# working.net
KiCad netlist of a schematic drawn in EAGLE
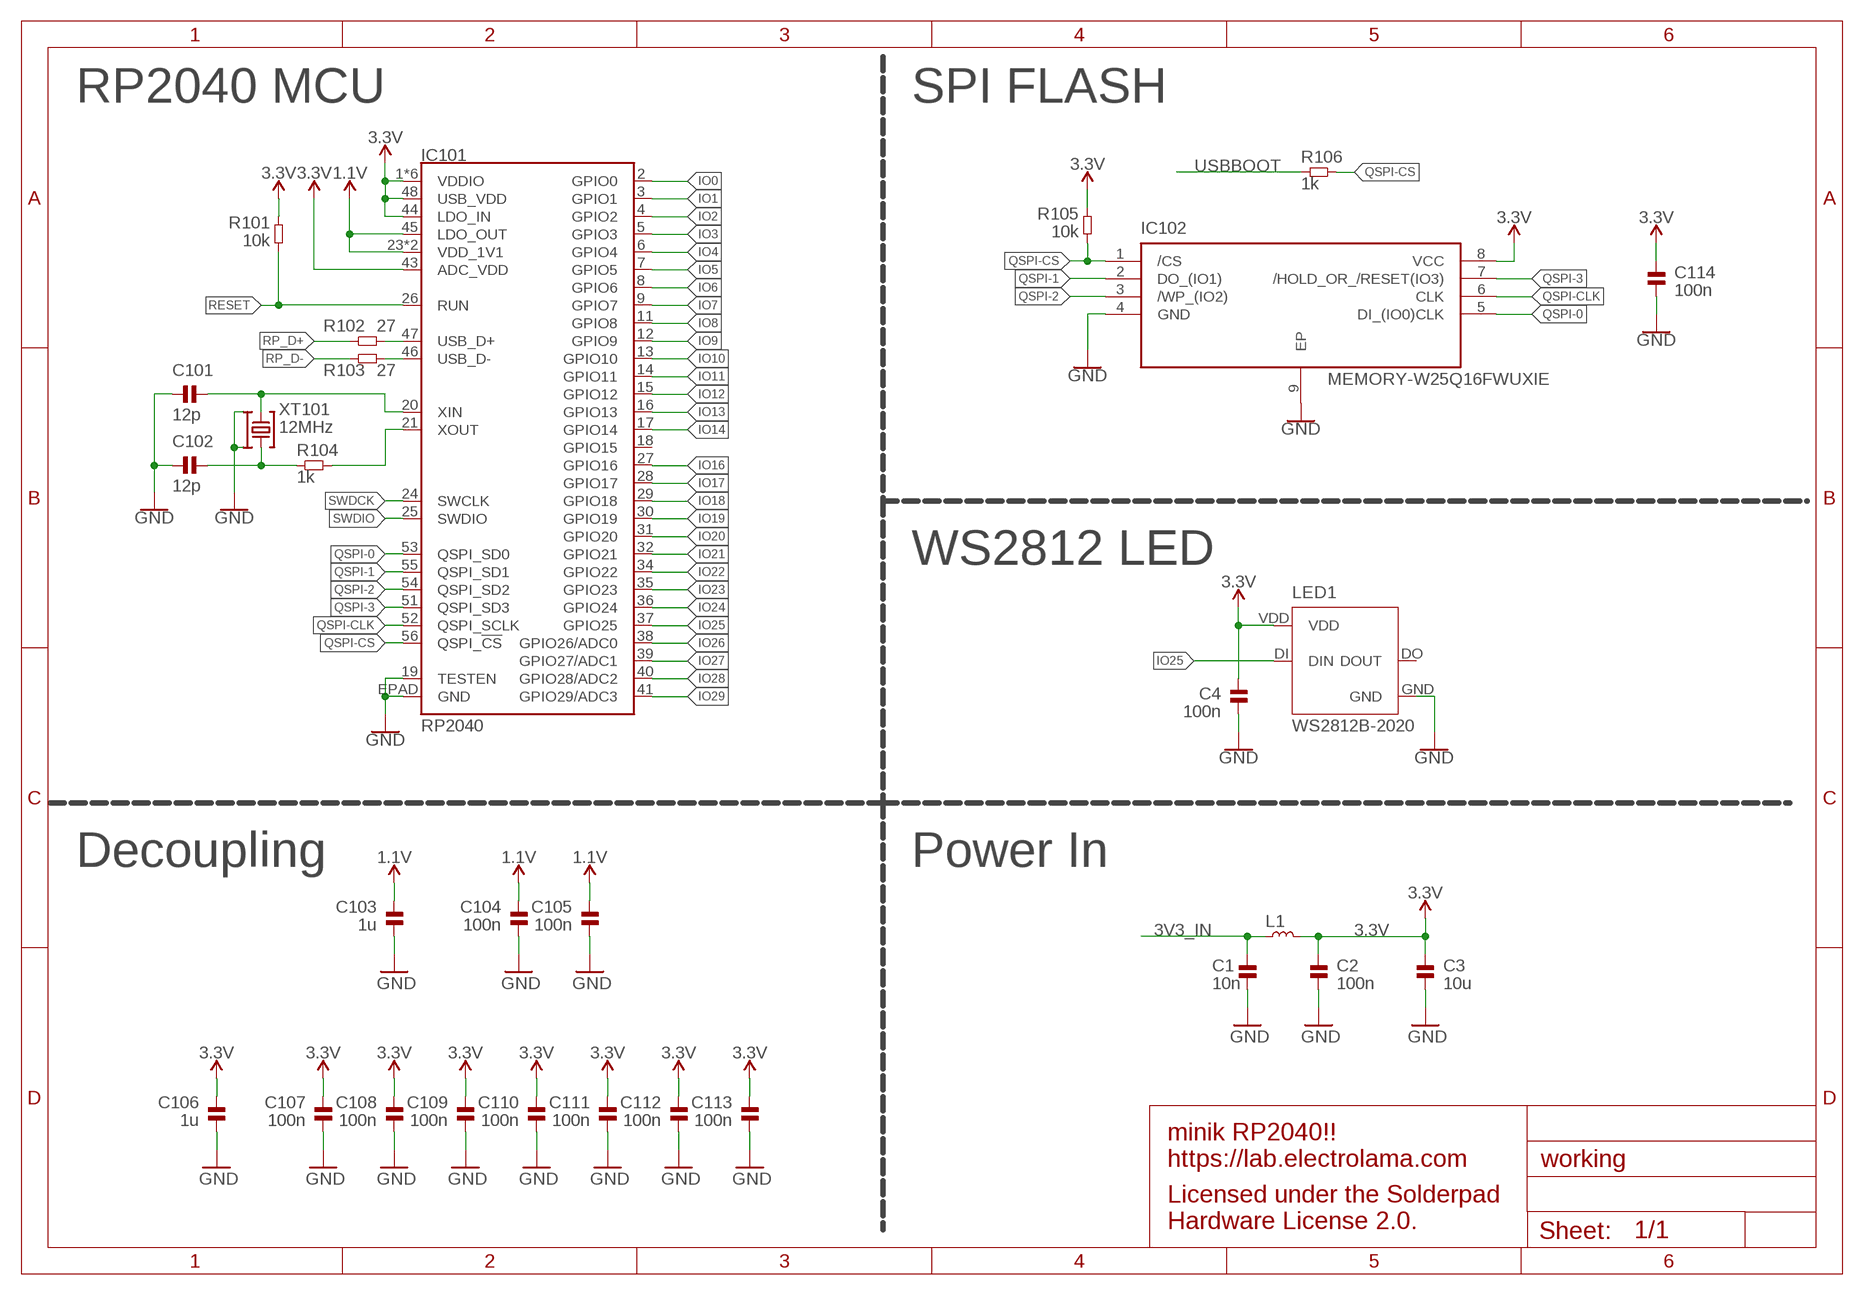
[diagram p0: schematic, sheet 1]

(export (version "E")
  (design (tool "Eeschema 10.0.6"))
  (components
    (comp (ref "C1")
      (value "10n")
      (footprint "eagle-import:_PKG_C_0402")
      (libsource (lib "eagle-import") (part "CAP-0402"))
    )
    (comp (ref "C2")
      (value "100n")
      (footprint "eagle-import:_PKG_C_0402")
      (libsource (lib "eagle-import") (part "CAP-0402"))
    )
    (comp (ref "C3")
      (value "10u")
      (footprint "eagle-import:_PKG_C_0402")
      (libsource (lib "eagle-import") (part "CAP-0402"))
    )
    (comp (ref "C4")
      (value "100n")
      (footprint "eagle-import:_PKG_C_0402")
      (libsource (lib "eagle-import") (part "CAP-0402"))
    )
    (comp (ref "C101")
      (value "12p")
      (footprint "eagle-import:_PKG_C_0402")
      (libsource (lib "eagle-import") (part "CAP-0402"))
    )
    (comp (ref "C102")
      (value "12p")
      (footprint "eagle-import:_PKG_C_0402")
      (libsource (lib "eagle-import") (part "CAP-0402"))
    )
    (comp (ref "C103")
      (value "1u")
      (footprint "eagle-import:_PKG_C_0402")
      (libsource (lib "eagle-import") (part "CAP-0402"))
    )
    (comp (ref "C104")
      (value "100n")
      (footprint "eagle-import:_PKG_C_0402")
      (libsource (lib "eagle-import") (part "CAP-0402"))
    )
    (comp (ref "C105")
      (value "100n")
      (footprint "eagle-import:_PKG_C_0402")
      (libsource (lib "eagle-import") (part "CAP-0402"))
    )
    (comp (ref "C106")
      (value "1u")
      (footprint "eagle-import:_PKG_C_0402")
      (libsource (lib "eagle-import") (part "CAP-0402"))
    )
    (comp (ref "C107")
      (value "100n")
      (footprint "eagle-import:_PKG_C_0402")
      (libsource (lib "eagle-import") (part "CAP-0402"))
    )
    (comp (ref "C108")
      (value "100n")
      (footprint "eagle-import:_PKG_C_0402")
      (libsource (lib "eagle-import") (part "CAP-0402"))
    )
    (comp (ref "C109")
      (value "100n")
      (footprint "eagle-import:_PKG_C_0402")
      (libsource (lib "eagle-import") (part "CAP-0402"))
    )
    (comp (ref "C110")
      (value "100n")
      (footprint "eagle-import:_PKG_C_0402")
      (libsource (lib "eagle-import") (part "CAP-0402"))
    )
    (comp (ref "C111")
      (value "100n")
      (footprint "eagle-import:_PKG_C_0402")
      (libsource (lib "eagle-import") (part "CAP-0402"))
    )
    (comp (ref "C112")
      (value "100n")
      (footprint "eagle-import:_PKG_C_0402")
      (libsource (lib "eagle-import") (part "CAP-0402"))
    )
    (comp (ref "C113")
      (value "100n")
      (footprint "eagle-import:_PKG_C_0402")
      (libsource (lib "eagle-import") (part "CAP-0402"))
    )
    (comp (ref "C114")
      (value "100n")
      (footprint "eagle-import:_PKG_C_0402")
      (libsource (lib "eagle-import") (part "CAP-0402"))
    )
    (comp (ref "IC101")
      (value "RP2040")
      (footprint "eagle-import:QFN-56")
      (libsource (lib "eagle-import") (part "RP2040"))
    )
    (comp (ref "IC102")
      (value "MEMORY-W25Q16FWUXIE")
      (footprint "eagle-import:SON50P300X200X60-9N")
      (fields
        (field (name "ARROW_PART_NUMBER") "W25Q16FWUXIE TR")
        (field (name "MOUSER_PART_NUMBER") "454-W25Q16FWUXIETR")
      )
      (libsource (lib "eagle-import") (part "MEMORY-W25Q16FWUXIE"))
    )
    (comp (ref "L1")
      (value "INDUCTOR-0402")
      (footprint "eagle-import:_PKG_L_0402")
      (libsource (lib "eagle-import") (part "INDUCTOR-0402"))
    )
    (comp (ref "LED1")
      (value "WS2812B-2020")
      (footprint "eagle-import:WS2812B-2020")
      (libsource (lib "eagle-import") (part "WS2812B-2020"))
    )
    (comp (ref "R101")
      (value "10k")
      (footprint "eagle-import:_PKG_R_0402")
      (libsource (lib "eagle-import") (part "RES-0402"))
    )
    (comp (ref "R102")
      (value "27")
      (footprint "eagle-import:_PKG_R_0402")
      (libsource (lib "eagle-import") (part "RES-0402"))
    )
    (comp (ref "R103")
      (value "27")
      (footprint "eagle-import:_PKG_R_0402")
      (libsource (lib "eagle-import") (part "RES-0402"))
    )
    (comp (ref "R104")
      (value "1k")
      (footprint "eagle-import:_PKG_R_0402")
      (libsource (lib "eagle-import") (part "RES-0402"))
    )
    (comp (ref "R105")
      (value "10k")
      (footprint "eagle-import:_PKG_R_0402")
      (libsource (lib "eagle-import") (part "RES-0402"))
    )
    (comp (ref "R106")
      (value "1k")
      (footprint "eagle-import:_PKG_R_0402")
      (libsource (lib "eagle-import") (part "RES-0402"))
    )
    (comp (ref "XT101")
      (value "12MHz")
      (footprint "eagle-import:XTAL-4P-3225")
      (libsource (lib "eagle-import") (part "XTAL-4P-3225"))
    )
  )
  (nets
    (net (code "1") (name "/3V3_IN") (class "Default")
      (node (ref "C1") (pin "2") (pinfunction "2_2") (pintype "passive"))
      (node (ref "L1") (pin "1") (pinfunction "1_1") (pintype "passive"))
    )
    (net (code "2") (name "/USBBOOT") (class "Default")
      (node (ref "R106") (pin "2") (pinfunction "2_2") (pintype "passive"))
    )
    (net (code "3") (name "1.1V") (class "Default")
      (node (ref "C103") (pin "2") (pinfunction "2_2") (pintype "passive"))
      (node (ref "C104") (pin "2") (pinfunction "2_2") (pintype "passive"))
      (node (ref "C105") (pin "2") (pinfunction "2_2") (pintype "passive"))
      (node (ref "IC101") (pin "23") (pinfunction "VDD_1V1_23") (pintype "bidirectional"))
      (node (ref "IC101") (pin "45") (pinfunction "LDO_OUT_45") (pintype "bidirectional"))
      (node (ref "IC101") (pin "50") (pinfunction "VDD_1V1_50") (pintype "bidirectional"))
    )
    (net (code "4") (name "3.3V") (class "Default")
      (node (ref "C106") (pin "2") (pinfunction "2_2") (pintype "passive"))
      (node (ref "C107") (pin "2") (pinfunction "2_2") (pintype "passive"))
      (node (ref "C108") (pin "2") (pinfunction "2_2") (pintype "passive"))
      (node (ref "C109") (pin "2") (pinfunction "2_2") (pintype "passive"))
      (node (ref "C110") (pin "2") (pinfunction "2_2") (pintype "passive"))
      (node (ref "C111") (pin "2") (pinfunction "2_2") (pintype "passive"))
      (node (ref "C112") (pin "2") (pinfunction "2_2") (pintype "passive"))
      (node (ref "C113") (pin "2") (pinfunction "2_2") (pintype "passive"))
      (node (ref "C114") (pin "2") (pinfunction "2_2") (pintype "passive"))
      (node (ref "C2") (pin "2") (pinfunction "2_2") (pintype "passive"))
      (node (ref "C3") (pin "2") (pinfunction "2_2") (pintype "passive"))
      (node (ref "C4") (pin "2") (pinfunction "2_2") (pintype "passive"))
      (node (ref "IC101") (pin "1") (pinfunction "VDDIO_1") (pintype "bidirectional"))
      (node (ref "IC101") (pin "10") (pinfunction "VDDIO_10") (pintype "bidirectional"))
      (node (ref "IC101") (pin "22") (pinfunction "VDDIO_22") (pintype "bidirectional"))
      (node (ref "IC101") (pin "33") (pinfunction "VDDIO_33") (pintype "bidirectional"))
      (node (ref "IC101") (pin "42") (pinfunction "VDDIO_42") (pintype "bidirectional"))
      (node (ref "IC101") (pin "43") (pinfunction "ADC_VDD_43") (pintype "bidirectional"))
      (node (ref "IC101") (pin "44") (pinfunction "LDO_IN_44") (pintype "bidirectional"))
      (node (ref "IC101") (pin "48") (pinfunction "USB_VDD_48") (pintype "bidirectional"))
      (node (ref "IC101") (pin "49") (pinfunction "VDDIO_49") (pintype "bidirectional"))
      (node (ref "IC102") (pin "8") (pinfunction "VCC_8") (pintype "bidirectional"))
      (node (ref "L1") (pin "2") (pinfunction "2_2") (pintype "passive"))
      (node (ref "LED1") (pin "VDD") (pinfunction "VDD_VDD") (pintype "bidirectional"))
      (node (ref "R101") (pin "2") (pinfunction "2_2") (pintype "passive"))
      (node (ref "R105") (pin "2") (pinfunction "2_2") (pintype "passive"))
    )
    (net (code "5") (name "GND") (class "Default")
      (node (ref "C1") (pin "1") (pinfunction "1_1") (pintype "passive"))
      (node (ref "C101") (pin "1") (pinfunction "1_1") (pintype "passive"))
      (node (ref "C102") (pin "1") (pinfunction "1_1") (pintype "passive"))
      (node (ref "C103") (pin "1") (pinfunction "1_1") (pintype "passive"))
      (node (ref "C104") (pin "1") (pinfunction "1_1") (pintype "passive"))
      (node (ref "C105") (pin "1") (pinfunction "1_1") (pintype "passive"))
      (node (ref "C106") (pin "1") (pinfunction "1_1") (pintype "passive"))
      (node (ref "C107") (pin "1") (pinfunction "1_1") (pintype "passive"))
      (node (ref "C108") (pin "1") (pinfunction "1_1") (pintype "passive"))
      (node (ref "C109") (pin "1") (pinfunction "1_1") (pintype "passive"))
      (node (ref "C110") (pin "1") (pinfunction "1_1") (pintype "passive"))
      (node (ref "C111") (pin "1") (pinfunction "1_1") (pintype "passive"))
      (node (ref "C112") (pin "1") (pinfunction "1_1") (pintype "passive"))
      (node (ref "C113") (pin "1") (pinfunction "1_1") (pintype "passive"))
      (node (ref "C114") (pin "1") (pinfunction "1_1") (pintype "passive"))
      (node (ref "C2") (pin "1") (pinfunction "1_1") (pintype "passive"))
      (node (ref "C3") (pin "1") (pinfunction "1_1") (pintype "passive"))
      (node (ref "C4") (pin "1") (pinfunction "1_1") (pintype "passive"))
      (node (ref "IC101") (pin "19") (pinfunction "TESTEN_19") (pintype "bidirectional"))
      (node (ref "IC101") (pin "EPAD") (pinfunction "GND_EPAD") (pintype "bidirectional"))
      (node (ref "IC102") (pin "4") (pinfunction "GND_4") (pintype "bidirectional"))
      (node (ref "IC102") (pin "9") (pinfunction "EP_9") (pintype "bidirectional"))
      (node (ref "LED1") (pin "GND") (pinfunction "GND_GND") (pintype "bidirectional"))
      (node (ref "XT101") (pin "2") (pinfunction "2_2") (pintype "bidirectional"))
      (node (ref "XT101") (pin "4") (pinfunction "4_4") (pintype "bidirectional"))
    )
    (net (code "6") (name "IO0") (class "Default")
      (node (ref "IC101") (pin "2") (pinfunction "GPIO0_2") (pintype "bidirectional"))
    )
    (net (code "7") (name "IO1") (class "Default")
      (node (ref "IC101") (pin "3") (pinfunction "GPIO1_3") (pintype "bidirectional"))
    )
    (net (code "8") (name "IO2") (class "Default")
      (node (ref "IC101") (pin "4") (pinfunction "GPIO2_4") (pintype "bidirectional"))
    )
    (net (code "9") (name "IO3") (class "Default")
      (node (ref "IC101") (pin "5") (pinfunction "GPIO3_5") (pintype "bidirectional"))
    )
    (net (code "10") (name "IO4") (class "Default")
      (node (ref "IC101") (pin "6") (pinfunction "GPIO4_6") (pintype "bidirectional"))
    )
    (net (code "11") (name "IO5") (class "Default")
      (node (ref "IC101") (pin "7") (pinfunction "GPIO5_7") (pintype "bidirectional"))
    )
    (net (code "12") (name "IO6") (class "Default")
      (node (ref "IC101") (pin "8") (pinfunction "GPIO6_8") (pintype "bidirectional"))
    )
    (net (code "13") (name "IO7") (class "Default")
      (node (ref "IC101") (pin "9") (pinfunction "GPIO7_9") (pintype "bidirectional"))
    )
    (net (code "14") (name "IO8") (class "Default")
      (node (ref "IC101") (pin "11") (pinfunction "GPIO8_11") (pintype "bidirectional"))
    )
    (net (code "15") (name "IO9") (class "Default")
      (node (ref "IC101") (pin "12") (pinfunction "GPIO9_12") (pintype "bidirectional"))
    )
    (net (code "16") (name "IO10") (class "Default")
      (node (ref "IC101") (pin "13") (pinfunction "GPIO10_13") (pintype "bidirectional"))
    )
    (net (code "17") (name "IO11") (class "Default")
      (node (ref "IC101") (pin "14") (pinfunction "GPIO11_14") (pintype "bidirectional"))
    )
    (net (code "18") (name "IO12") (class "Default")
      (node (ref "IC101") (pin "15") (pinfunction "GPIO12_15") (pintype "bidirectional"))
    )
    (net (code "19") (name "IO13") (class "Default")
      (node (ref "IC101") (pin "16") (pinfunction "GPIO13_16") (pintype "bidirectional"))
    )
    (net (code "20") (name "IO14") (class "Default")
      (node (ref "IC101") (pin "17") (pinfunction "GPIO14_17") (pintype "bidirectional"))
    )
    (net (code "21") (name "IO16") (class "Default")
      (node (ref "IC101") (pin "27") (pinfunction "GPIO16_27") (pintype "bidirectional"))
    )
    (net (code "22") (name "IO17") (class "Default")
      (node (ref "IC101") (pin "28") (pinfunction "GPIO17_28") (pintype "bidirectional"))
    )
    (net (code "23") (name "IO18") (class "Default")
      (node (ref "IC101") (pin "29") (pinfunction "GPIO18_29") (pintype "bidirectional"))
    )
    (net (code "24") (name "IO19") (class "Default")
      (node (ref "IC101") (pin "30") (pinfunction "GPIO19_30") (pintype "bidirectional"))
    )
    (net (code "25") (name "IO20") (class "Default")
      (node (ref "IC101") (pin "31") (pinfunction "GPIO20_31") (pintype "bidirectional"))
    )
    (net (code "26") (name "IO21") (class "Default")
      (node (ref "IC101") (pin "32") (pinfunction "GPIO21_32") (pintype "bidirectional"))
    )
    (net (code "27") (name "IO22") (class "Default")
      (node (ref "IC101") (pin "34") (pinfunction "GPIO22_34") (pintype "bidirectional"))
    )
    (net (code "28") (name "IO23") (class "Default")
      (node (ref "IC101") (pin "35") (pinfunction "GPIO23_35") (pintype "bidirectional"))
    )
    (net (code "29") (name "IO24") (class "Default")
      (node (ref "IC101") (pin "36") (pinfunction "GPIO24_36") (pintype "bidirectional"))
    )
    (net (code "30") (name "IO25") (class "Default")
      (node (ref "IC101") (pin "37") (pinfunction "GPIO25_37") (pintype "bidirectional"))
      (node (ref "LED1") (pin "DI") (pinfunction "DIN_DI") (pintype "bidirectional"))
    )
    (net (code "31") (name "IO26") (class "Default")
      (node (ref "IC101") (pin "38") (pinfunction "GPIO26/ADC0_38") (pintype "bidirectional"))
    )
    (net (code "32") (name "IO27") (class "Default")
      (node (ref "IC101") (pin "39") (pinfunction "GPIO27/ADC1_39") (pintype "bidirectional"))
    )
    (net (code "33") (name "IO28") (class "Default")
      (node (ref "IC101") (pin "40") (pinfunction "GPIO28/ADC2_40") (pintype "bidirectional"))
    )
    (net (code "34") (name "IO29") (class "Default")
      (node (ref "IC101") (pin "41") (pinfunction "GPIO29/ADC3_41") (pintype "bidirectional"))
    )
    (net (code "35") (name "Net-(C102-Pad2)") (class "Default")
      (node (ref "C102") (pin "2") (pinfunction "2_2") (pintype "passive"))
      (node (ref "R104") (pin "1") (pinfunction "1_1") (pintype "passive"))
      (node (ref "XT101") (pin "1") (pinfunction "1_1") (pintype "passive"))
    )
    (net (code "36") (name "Net-(IC101-USB_D+)") (class "Default")
      (node (ref "IC101") (pin "47") (pinfunction "USB_D+_47") (pintype "bidirectional"))
      (node (ref "R102") (pin "2") (pinfunction "2_2") (pintype "passive"))
    )
    (net (code "37") (name "Net-(IC101-USB_D-)") (class "Default")
      (node (ref "IC101") (pin "46") (pinfunction "USB_D-_46") (pintype "bidirectional"))
      (node (ref "R103") (pin "2") (pinfunction "2_2") (pintype "passive"))
    )
    (net (code "38") (name "Net-(IC101-XIN)") (class "Default")
      (node (ref "C101") (pin "2") (pinfunction "2_2") (pintype "passive"))
      (node (ref "IC101") (pin "20") (pinfunction "XIN_20") (pintype "bidirectional"))
      (node (ref "XT101") (pin "3") (pinfunction "3_3") (pintype "passive"))
    )
    (net (code "39") (name "Net-(IC101-XOUT)") (class "Default")
      (node (ref "IC101") (pin "21") (pinfunction "XOUT_21") (pintype "bidirectional"))
      (node (ref "R104") (pin "2") (pinfunction "2_2") (pintype "passive"))
    )
    (net (code "40") (name "QSPI-0") (class "Default")
      (node (ref "IC101") (pin "53") (pinfunction "QSPI_SD0_53") (pintype "bidirectional"))
      (node (ref "IC102") (pin "5") (pinfunction "DI_(IO0)CLK_5") (pintype "bidirectional"))
    )
    (net (code "41") (name "QSPI-1") (class "Default")
      (node (ref "IC101") (pin "55") (pinfunction "QSPI_SD1_55") (pintype "bidirectional"))
      (node (ref "IC102") (pin "2") (pinfunction "DO_(IO1)_2") (pintype "bidirectional"))
    )
    (net (code "42") (name "QSPI-2") (class "Default")
      (node (ref "IC101") (pin "54") (pinfunction "QSPI_SD2_54") (pintype "bidirectional"))
      (node (ref "IC102") (pin "3") (pinfunction "/WP_(IO2)_3") (pintype "bidirectional"))
    )
    (net (code "43") (name "QSPI-3") (class "Default")
      (node (ref "IC101") (pin "51") (pinfunction "QSPI_SD3_51") (pintype "bidirectional"))
      (node (ref "IC102") (pin "7") (pinfunction "/HOLD_OR_/RESET(IO3)_7") (pintype "bidirectional"))
    )
    (net (code "44") (name "QSPI-CLK") (class "Default")
      (node (ref "IC101") (pin "52") (pinfunction "QSPI_SCLK_52") (pintype "bidirectional"))
      (node (ref "IC102") (pin "6") (pinfunction "CLK_6") (pintype "bidirectional"))
    )
    (net (code "45") (name "QSPI-CS") (class "Default")
      (node (ref "IC101") (pin "56") (pinfunction "QSPI_~{CS}_56") (pintype "bidirectional"))
      (node (ref "IC102") (pin "1") (pinfunction "/CS_1") (pintype "bidirectional"))
      (node (ref "R105") (pin "1") (pinfunction "1_1") (pintype "passive"))
      (node (ref "R106") (pin "1") (pinfunction "1_1") (pintype "passive"))
    )
    (net (code "46") (name "RESET") (class "Default")
      (node (ref "IC101") (pin "26") (pinfunction "RUN_26") (pintype "bidirectional"))
      (node (ref "R101") (pin "1") (pinfunction "1_1") (pintype "passive"))
    )
    (net (code "47") (name "RP_D+") (class "Default")
      (node (ref "R102") (pin "1") (pinfunction "1_1") (pintype "passive"))
    )
    (net (code "48") (name "RP_D-") (class "Default")
      (node (ref "R103") (pin "1") (pinfunction "1_1") (pintype "passive"))
    )
    (net (code "49") (name "SWDCK") (class "Default")
      (node (ref "IC101") (pin "24") (pinfunction "SWCLK_24") (pintype "bidirectional"))
    )
    (net (code "50") (name "SWDIO") (class "Default")
      (node (ref "IC101") (pin "25") (pinfunction "SWDIO_25") (pintype "bidirectional"))
    )
    (net (code "51") (name "unconnected-(IC101-GPIO15-Pad18)") (class "Default")
      (node (ref "IC101") (pin "18") (pinfunction "GPIO15_18") (pintype "bidirectional"))
    )
    (net (code "52") (name "unconnected-(LED1-DOUT-PadDO)") (class "Default")
      (node (ref "LED1") (pin "DO") (pinfunction "DOUT_DO") (pintype "bidirectional"))
    )
  )
)
